# LED.net
KiCad netlist of a schematic drawn in EAGLE
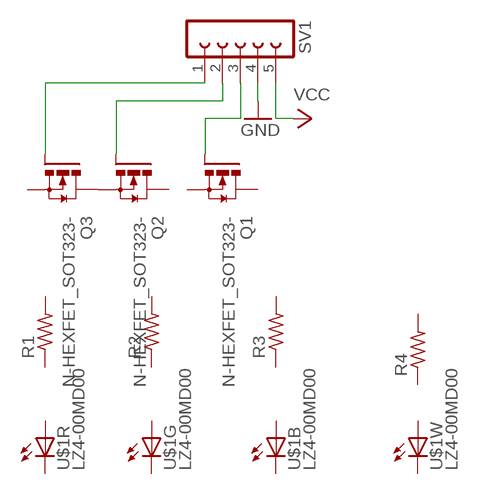
[diagram p0: schematic, sheet 1]

(export (version "E")
  (design (tool "Eeschema 10.0.6"))
  (components
    (comp (ref "Q1")
      (value "N-HEXFET_SOT323-")
      (footprint "eagle-import:SOT223")
      (libsource (lib "eagle-import") (part "N-HEXFET_?-SOT323"))
    )
    (comp (ref "Q2")
      (value "N-HEXFET_SOT323-")
      (footprint "eagle-import:SOT223")
      (libsource (lib "eagle-import") (part "N-HEXFET_?-SOT323"))
    )
    (comp (ref "Q3")
      (value "N-HEXFET_SOT323-")
      (footprint "eagle-import:SOT223")
      (libsource (lib "eagle-import") (part "N-HEXFET_?-SOT323"))
    )
    (comp (ref "R1")
      (value "R-US_0204/7")
      (footprint "eagle-import:0204_7")
      (libsource (lib "eagle-import") (part "R-US_0204/7"))
    )
    (comp (ref "R2")
      (value "R-US_0204/7")
      (footprint "eagle-import:0204_7")
      (libsource (lib "eagle-import") (part "R-US_0204/7"))
    )
    (comp (ref "R3")
      (value "R-US_0204/7")
      (footprint "eagle-import:0204_7")
      (libsource (lib "eagle-import") (part "R-US_0204/7"))
    )
    (comp (ref "R4")
      (value "R-US_0204/7")
      (footprint "eagle-import:0204_7")
      (libsource (lib "eagle-import") (part "R-US_0204/7"))
    )
    (comp (ref "SV1")
      (value "FE05-1")
      (footprint "eagle-import:FE05-1")
      (libsource (lib "eagle-import") (part "FE05-1"))
    )
    (comp (ref "U$1")
      (value "LZ4-00MD00")
      (footprint "eagle-import:LZ4-00MD0")
      (libsource (lib "eagle-import") (part "LZ4-00MD00"))
    )
  )
  (nets
    (net (code "1") (name "GND") (class "Default")
      (node (ref "SV1") (pin "4") (pinfunction "4_4") (pintype "passive"))
    )
    (net (code "2") (name "Net-(Q1-G)") (class "Default")
      (node (ref "Q1") (pin "1") (pinfunction "G_1") (pintype "passive"))
      (node (ref "SV1") (pin "3") (pinfunction "3_3") (pintype "passive"))
    )
    (net (code "3") (name "Net-(Q2-G)") (class "Default")
      (node (ref "Q2") (pin "1") (pinfunction "G_1") (pintype "passive"))
      (node (ref "SV1") (pin "2") (pinfunction "2_2") (pintype "passive"))
    )
    (net (code "4") (name "Net-(Q2-S)") (class "Default")
      (node (ref "Q2") (pin "3") (pinfunction "S_3") (pintype "passive"))
      (node (ref "Q3") (pin "4") (pinfunction "D_4") (pintype "passive"))
    )
    (net (code "5") (name "Net-(Q3-G)") (class "Default")
      (node (ref "Q3") (pin "1") (pinfunction "G_1") (pintype "passive"))
      (node (ref "SV1") (pin "1") (pinfunction "1_1") (pintype "passive"))
    )
    (net (code "6") (name "VCC") (class "Default")
      (node (ref "SV1") (pin "5") (pinfunction "5_5") (pintype "passive"))
    )
    (net (code "7") (name "unconnected-(Q1-D-Pad4)") (class "Default")
      (node (ref "Q1") (pin "4") (pinfunction "D_4") (pintype "passive"))
    )
    (net (code "8") (name "unconnected-(Q1-S-Pad3)") (class "Default")
      (node (ref "Q1") (pin "3") (pinfunction "S_3") (pintype "passive"))
    )
    (net (code "9") (name "unconnected-(Q2-D-Pad4)") (class "Default")
      (node (ref "Q2") (pin "4") (pinfunction "D_4") (pintype "passive"))
    )
    (net (code "10") (name "unconnected-(Q3-S-Pad3)") (class "Default")
      (node (ref "Q3") (pin "3") (pinfunction "S_3") (pintype "passive"))
    )
    (net (code "11") (name "unconnected-(R1-Pad1)") (class "Default")
      (node (ref "R1") (pin "1") (pinfunction "1_1") (pintype "passive"))
    )
    (net (code "12") (name "unconnected-(R1-Pad2)") (class "Default")
      (node (ref "R1") (pin "2") (pinfunction "2_2") (pintype "passive"))
    )
    (net (code "13") (name "unconnected-(R2-Pad1)") (class "Default")
      (node (ref "R2") (pin "1") (pinfunction "1_1") (pintype "passive"))
    )
    (net (code "14") (name "unconnected-(R2-Pad2)") (class "Default")
      (node (ref "R2") (pin "2") (pinfunction "2_2") (pintype "passive"))
    )
    (net (code "15") (name "unconnected-(R3-Pad1)") (class "Default")
      (node (ref "R3") (pin "1") (pinfunction "1_1") (pintype "passive"))
    )
    (net (code "16") (name "unconnected-(R3-Pad2)") (class "Default")
      (node (ref "R3") (pin "2") (pinfunction "2_2") (pintype "passive"))
    )
    (net (code "17") (name "unconnected-(R4-Pad1)") (class "Default")
      (node (ref "R4") (pin "1") (pinfunction "1_1") (pintype "passive"))
    )
    (net (code "18") (name "unconnected-(R4-Pad2)") (class "Default")
      (node (ref "R4") (pin "2") (pinfunction "2_2") (pintype "passive"))
    )
    (net (code "19") (name "unconnected-(U$1A-A-Pad7)") (class "Default")
      (node (ref "U$1") (pin "7") (pinfunction "A_7") (pintype "passive"))
    )
    (net (code "20") (name "unconnected-(U$1A-C-Pad8)") (class "Default")
      (node (ref "U$1") (pin "8") (pinfunction "C_8") (pintype "passive"))
    )
    (net (code "21") (name "unconnected-(U$1B-A-Pad5)") (class "Default")
      (node (ref "U$1") (pin "5") (pinfunction "A_5") (pintype "passive"))
    )
    (net (code "22") (name "unconnected-(U$1B-C-Pad6)") (class "Default")
      (node (ref "U$1") (pin "6") (pinfunction "C_6") (pintype "passive"))
    )
    (net (code "23") (name "unconnected-(U$1C-A-Pad3)") (class "Default")
      (node (ref "U$1") (pin "3") (pinfunction "A_3") (pintype "passive"))
    )
    (net (code "24") (name "unconnected-(U$1C-C-Pad4)") (class "Default")
      (node (ref "U$1") (pin "4") (pinfunction "C_4") (pintype "passive"))
    )
    (net (code "25") (name "unconnected-(U$1D-A-Pad1)") (class "Default")
      (node (ref "U$1") (pin "1") (pinfunction "A_1") (pintype "passive"))
    )
    (net (code "26") (name "unconnected-(U$1D-C-Pad2)") (class "Default")
      (node (ref "U$1") (pin "2") (pinfunction "C_2") (pintype "passive"))
    )
  )
)
